# MCU152A_Connectors.net
KiCad netlist of a schematic drawn in Altium Designer
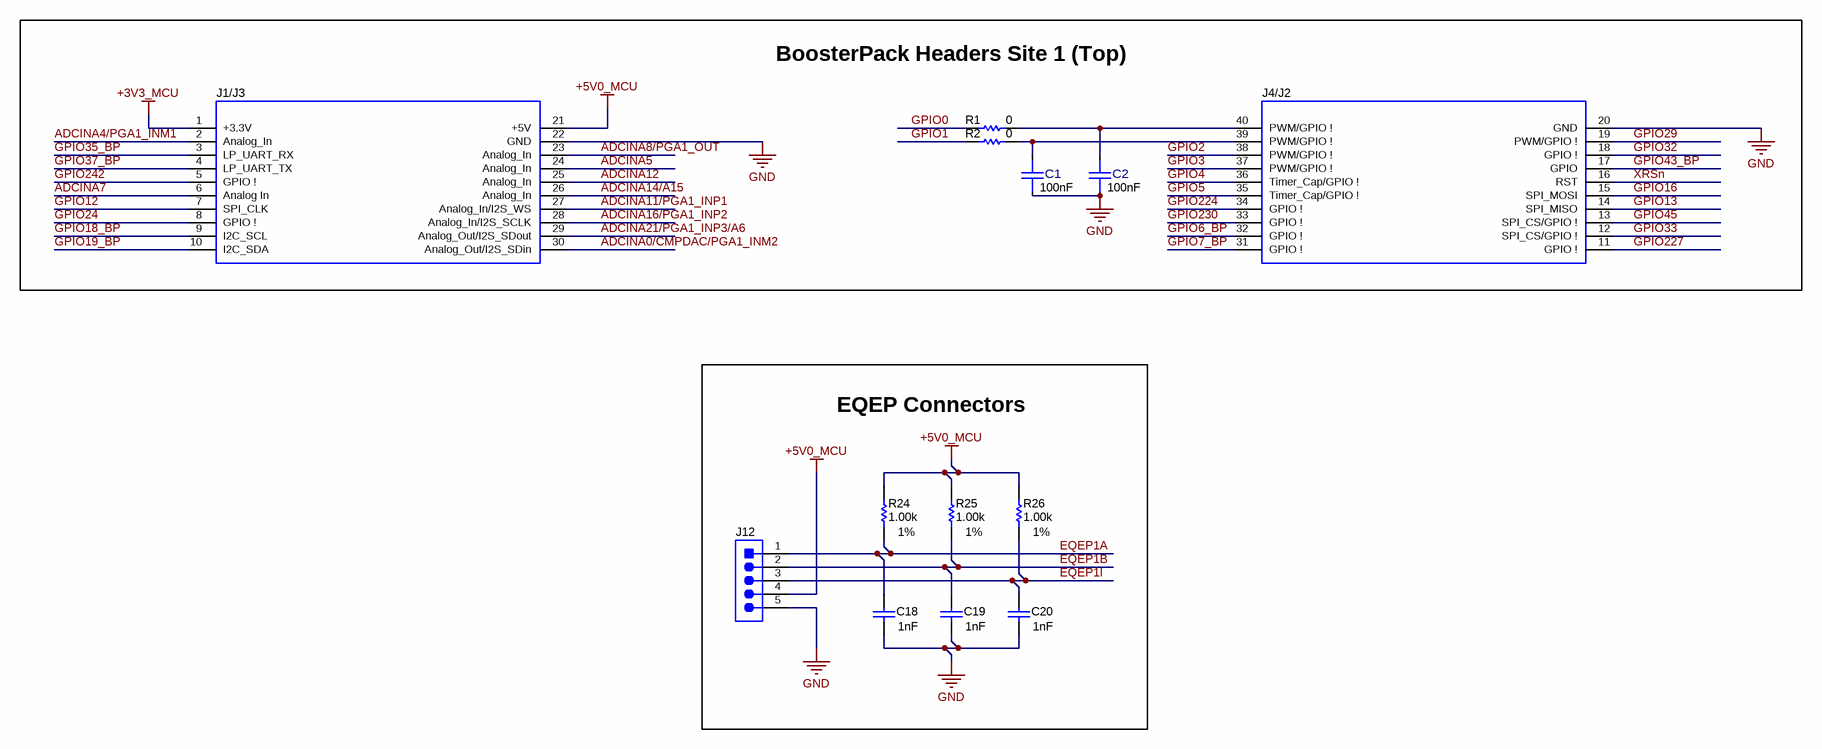
[diagram p0: MCU152A_Connectors.SchDoc]

(export (version "E")
  (design (tool "Eeschema 10.0.6"))
  (components
    (comp (ref "C1")
      (value "885012205018")
      (footprint "FP-885012205018_0402-MFG")
      (description "0.1µF ±10% 10V Ceramic Capacitor X7R 0402 (1005 Metric)")
      (fields
        (field (name "MANUFACTURER") "Wurth Electronics")
        (field (name "MOUSER PART NUMBER") "710-885012205018")
        (field (name "CAP_F") "100nF")
      )
      (libsource (lib "Altium Vault - TI") (part "SYM-885012205018"))
    )
    (comp (ref "C2")
      (value "885012205018")
      (footprint "FP-885012205018_0402-MFG")
      (description "0.1µF ±10% 10V Ceramic Capacitor X7R 0402 (1005 Metric)")
      (fields
        (field (name "MANUFACTURER") "Wurth Electronics")
        (field (name "MOUSER PART NUMBER") "710-885012205018")
        (field (name "CAP_F") "100nF")
      )
      (libsource (lib "Altium Vault - TI") (part "SYM-885012205018"))
    )
    (comp (ref "C18")
      (value "885012205061")
      (footprint "0402")
      (description "CAP, CERM, 1000 pF, 50 V, +/- 10%, X7R, 0402")
      (fields
        (field (name "MANUFACTURER") "Wurth Elektronik")
        (field (name "CAP_F") "1nF")
        (field (name "PUBLISHER") "Texas Instruments")
      )
      (libsource (lib "Altium Vault - TI") (part "Capacitor"))
    )
    (comp (ref "C19")
      (value "885012205061")
      (footprint "0402")
      (description "CAP, CERM, 1000 pF, 50 V, +/- 10%, X7R, 0402")
      (fields
        (field (name "MANUFACTURER") "Wurth Elektronik")
        (field (name "CAP_F") "1nF")
        (field (name "PUBLISHER") "Texas Instruments")
      )
      (libsource (lib "Altium Vault - TI") (part "Capacitor"))
    )
    (comp (ref "C20")
      (value "885012205061")
      (footprint "0402")
      (description "CAP, CERM, 1000 pF, 50 V, +/- 10%, X7R, 0402")
      (fields
        (field (name "MANUFACTURER") "Wurth Elektronik")
        (field (name "CAP_F") "1nF")
        (field (name "PUBLISHER") "Texas Instruments")
      )
      (libsource (lib "Altium Vault - TI") (part "Capacitor"))
    )
    (comp (ref "J1/J3")
      (value "SSQ-110-03-T-D")
      (footprint "BoosterPack_40pin_J1J3")
      (description "Receptacle, 2.54mm, 10x2, Tin, TH")
      (fields (field (name "ALTERNATE PARTNUMBER") "CRD-081413-A-G") (field (name "MANUFACTURER") "Samtec"))
      (libsource (lib "Altium Vault - TI") (part "BoosterPack_40pin_J1J3"))
    )
    (comp (ref "J4/J2")
      (value "SSQ-110-03-T-D")
      (footprint "BoosterPack_40pin_J2J4")
      (description "Receptacle, 2.54mm, 10x2, Tin, TH")
      (fields (field (name "ALTERNATE PARTNUMBER") "CRD-081413-A-G") (field (name "MANUFACTURER") "Samtec"))
      (libsource (lib "Altium Vault - TI") (part "BoosterPack_40pin_J2J4"))
    )
    (comp (ref "J12")
      (value "61300511121")
      (footprint "Wurth_61300511121")
      (description "Header, 2.54mm, 5x1, Gold, TH")
      (fields (field (name "MANUFACTURER") "Wurth Elektronik"))
      (libsource (lib "Altium Vault - TI") (part "Header_5x1"))
    )
    (comp (ref "R1")
      (value "RC0402JR-070RL")
      (footprint "0402")
      (description "RES, 0, 5%, 0.063 W, 0402")
      (fields
        (field (name "MANUFACTURER") "Yageo America")
        (field (name "VALUEDISPLAYED") "0")
        (field (name "PUBLISHER") "Texas Instruments")
      )
      (libsource (lib "Altium Vault - TI") (part "Resistor"))
    )
    (comp (ref "R2")
      (value "RC0402JR-070RL")
      (footprint "0402")
      (description "RES, 0, 5%, 0.063 W, 0402")
      (fields
        (field (name "MANUFACTURER") "Yageo America")
        (field (name "VALUEDISPLAYED") "0")
        (field (name "PUBLISHER") "Texas Instruments")
      )
      (libsource (lib "Altium Vault - TI") (part "Resistor"))
    )
    (comp (ref "R24")
      (value "CRCW04021K00FKED")
      (footprint "0402")
      (description "RES, 1.00 k, 1%, 0.063 W, AEC-Q200 Grade 0, 0402")
      (fields
        (field (name "VALUEDISPLAYED") "1.00k")
        (field (name "MANUFACTURER") "Vishay-Dale")
        (field (name "VALUE1") "1%")
      )
      (libsource (lib "Altium Vault - TI") (part "Resistor"))
    )
    (comp (ref "R25")
      (value "CRCW04021K00FKED")
      (footprint "0402")
      (description "RES, 1.00 k, 1%, 0.063 W, AEC-Q200 Grade 0, 0402")
      (fields
        (field (name "VALUEDISPLAYED") "1.00k")
        (field (name "MANUFACTURER") "Vishay-Dale")
        (field (name "VALUE1") "1%")
      )
      (libsource (lib "Altium Vault - TI") (part "Resistor"))
    )
    (comp (ref "R26")
      (value "CRCW04021K00FKED")
      (footprint "0402")
      (description "RES, 1.00 k, 1%, 0.063 W, AEC-Q200 Grade 0, 0402")
      (fields
        (field (name "VALUEDISPLAYED") "1.00k")
        (field (name "MANUFACTURER") "Vishay-Dale")
        (field (name "VALUE1") "1%")
      )
      (libsource (lib "Altium Vault - TI") (part "Resistor"))
    )
  )
  (nets
    (net (code "1") (name "+3V3_MCU") (class "Default")
      (node (ref "J1/J3") (pin "1") (pinfunction "+3.3V_1") (pintype "power_in"))
    )
    (net (code "2") (name "+5V0_MCU") (class "Default")
      (node (ref "J1/J3") (pin "21") (pinfunction "+5V_21") (pintype "power_in"))
      (node (ref "J12") (pin "4") (pinfunction "4_4") (pintype "passive"))
      (node (ref "R24") (pin "2") (pinfunction "2_2") (pintype "passive"))
      (node (ref "R25") (pin "2") (pinfunction "2_2") (pintype "passive"))
      (node (ref "R26") (pin "2") (pinfunction "2_2") (pintype "passive"))
    )
    (net (code "3") (name "/ADCINA0{slash}CMPDAC{slash}PGA1_INM2") (class "Default")
      (node (ref "J1/J3") (pin "30") (pinfunction "Analog_Out/I2S_SDin_30") (pintype "passive"))
    )
    (net (code "4") (name "/ADCINA4{slash}PGA1_INM1") (class "Default")
      (node (ref "J1/J3") (pin "2") (pinfunction "Analog_In_2") (pintype "passive"))
    )
    (net (code "5") (name "/ADCINA5") (class "Default")
      (node (ref "J1/J3") (pin "24") (pinfunction "Analog_In_24") (pintype "passive"))
    )
    (net (code "6") (name "/ADCINA7") (class "Default")
      (node (ref "J1/J3") (pin "6") (pinfunction "Analog_In_6") (pintype "passive"))
    )
    (net (code "7") (name "/ADCINA8{slash}PGA1_OUT") (class "Default")
      (node (ref "J1/J3") (pin "23") (pinfunction "Analog_In_23") (pintype "passive"))
    )
    (net (code "8") (name "/ADCINA11{slash}PGA1_INP1") (class "Default")
      (node (ref "J1/J3") (pin "27") (pinfunction "Analog_In/I2S_WS_27") (pintype "passive"))
    )
    (net (code "9") (name "/ADCINA12") (class "Default")
      (node (ref "J1/J3") (pin "25") (pinfunction "Analog_In_25") (pintype "passive"))
    )
    (net (code "10") (name "/ADCINA14{slash}A15") (class "Default")
      (node (ref "J1/J3") (pin "26") (pinfunction "Analog_In_26") (pintype "passive"))
    )
    (net (code "11") (name "/ADCINA16{slash}PGA1_INP2") (class "Default")
      (node (ref "J1/J3") (pin "28") (pinfunction "Analog_In/I2S_SCLK_28") (pintype "passive"))
    )
    (net (code "12") (name "/ADCINA21{slash}PGA1_INP3{slash}A6") (class "Default")
      (node (ref "J1/J3") (pin "29") (pinfunction "Analog_Out/I2S_SDout_29") (pintype "passive"))
    )
    (net (code "13") (name "/EQEP1A") (class "Default")
      (node (ref "C18") (pin "1") (pinfunction "1_1") (pintype "passive"))
      (node (ref "J12") (pin "1") (pinfunction "1_1") (pintype "passive"))
      (node (ref "R24") (pin "1") (pinfunction "1_1") (pintype "passive"))
    )
    (net (code "14") (name "/EQEP1B") (class "Default")
      (node (ref "C19") (pin "1") (pinfunction "1_1") (pintype "passive"))
      (node (ref "J12") (pin "2") (pinfunction "2_2") (pintype "passive"))
      (node (ref "R25") (pin "1") (pinfunction "1_1") (pintype "passive"))
    )
    (net (code "15") (name "/EQEP1I") (class "Default")
      (node (ref "C20") (pin "1") (pinfunction "1_1") (pintype "passive"))
      (node (ref "J12") (pin "3") (pinfunction "3_3") (pintype "passive"))
      (node (ref "R26") (pin "1") (pinfunction "1_1") (pintype "passive"))
    )
    (net (code "16") (name "/GPIO0") (class "Default")
      (node (ref "R1") (pin "1") (pinfunction "1_1") (pintype "passive"))
    )
    (net (code "17") (name "/GPIO1") (class "Default")
      (node (ref "R2") (pin "1") (pinfunction "1_1") (pintype "passive"))
    )
    (net (code "18") (name "/GPIO2") (class "Default")
      (node (ref "J4/J2") (pin "38") (pinfunction "PWM/GPIO_!_38") (pintype "passive"))
    )
    (net (code "19") (name "/GPIO3") (class "Default")
      (node (ref "J4/J2") (pin "37") (pinfunction "PWM/GPIO_!_37") (pintype "passive"))
    )
    (net (code "20") (name "/GPIO4") (class "Default")
      (node (ref "J4/J2") (pin "36") (pinfunction "Timer_Cap/GPIO_!_36") (pintype "passive"))
    )
    (net (code "21") (name "/GPIO5") (class "Default")
      (node (ref "J4/J2") (pin "35") (pinfunction "Timer_Cap/GPIO_!_35") (pintype "passive"))
    )
    (net (code "22") (name "/GPIO6_BP") (class "Default")
      (node (ref "J4/J2") (pin "32") (pinfunction "GPIO_!_32") (pintype "passive"))
    )
    (net (code "23") (name "/GPIO7_BP") (class "Default")
      (node (ref "J4/J2") (pin "31") (pinfunction "GPIO_!_31") (pintype "passive"))
    )
    (net (code "24") (name "/GPIO12") (class "Default")
      (node (ref "J1/J3") (pin "7") (pinfunction "SPI_CLK_7") (pintype "passive"))
    )
    (net (code "25") (name "/GPIO13") (class "Default")
      (node (ref "J4/J2") (pin "14") (pinfunction "SPI_MISO_14") (pintype "passive"))
    )
    (net (code "26") (name "/GPIO16") (class "Default")
      (node (ref "J4/J2") (pin "15") (pinfunction "SPI_MOSI_15") (pintype "passive"))
    )
    (net (code "27") (name "/GPIO18_BP") (class "Default")
      (node (ref "J1/J3") (pin "9") (pinfunction "I2C_SCL_9") (pintype "passive"))
    )
    (net (code "28") (name "/GPIO19_BP") (class "Default")
      (node (ref "J1/J3") (pin "10") (pinfunction "I2C_SDA_10") (pintype "passive"))
    )
    (net (code "29") (name "/GPIO24") (class "Default")
      (node (ref "J1/J3") (pin "8") (pinfunction "GPIO_!_8") (pintype "passive"))
    )
    (net (code "30") (name "/GPIO29") (class "Default")
      (node (ref "J4/J2") (pin "19") (pinfunction "PWM/GPIO_!_19") (pintype "passive"))
    )
    (net (code "31") (name "/GPIO32") (class "Default")
      (node (ref "J4/J2") (pin "18") (pinfunction "GPIO_!_18") (pintype "passive"))
    )
    (net (code "32") (name "/GPIO33") (class "Default")
      (node (ref "J4/J2") (pin "12") (pinfunction "SPI_CS/GPIO_!_12") (pintype "passive"))
    )
    (net (code "33") (name "/GPIO35_BP") (class "Default")
      (node (ref "J1/J3") (pin "3") (pinfunction "LP_UART_RX_3") (pintype "passive"))
    )
    (net (code "34") (name "/GPIO37_BP") (class "Default")
      (node (ref "J1/J3") (pin "4") (pinfunction "LP_UART_TX_4") (pintype "passive"))
    )
    (net (code "35") (name "/GPIO43_BP") (class "Default")
      (node (ref "J4/J2") (pin "17") (pinfunction "GPIO_17") (pintype "passive"))
    )
    (net (code "36") (name "/GPIO45") (class "Default")
      (node (ref "J4/J2") (pin "13") (pinfunction "SPI_CS/GPIO_!_13") (pintype "passive"))
    )
    (net (code "37") (name "/GPIO224") (class "Default")
      (node (ref "J4/J2") (pin "34") (pinfunction "GPIO_!_34") (pintype "passive"))
    )
    (net (code "38") (name "/GPIO227") (class "Default")
      (node (ref "J4/J2") (pin "11") (pinfunction "GPIO_!_11") (pintype "passive"))
    )
    (net (code "39") (name "/GPIO230") (class "Default")
      (node (ref "J4/J2") (pin "33") (pinfunction "GPIO_!_33") (pintype "passive"))
    )
    (net (code "40") (name "/GPIO242") (class "Default")
      (node (ref "J1/J3") (pin "5") (pinfunction "GPIO_!_5") (pintype "passive"))
    )
    (net (code "41") (name "/XRSn") (class "Default")
      (node (ref "J4/J2") (pin "16") (pinfunction "RST_16") (pintype "passive"))
    )
    (net (code "42") (name "GND") (class "Default")
      (node (ref "C1") (pin "1") (pinfunction "1_1") (pintype "passive"))
      (node (ref "C18") (pin "2") (pinfunction "2_2") (pintype "passive"))
      (node (ref "C19") (pin "2") (pinfunction "2_2") (pintype "passive"))
      (node (ref "C2") (pin "1") (pinfunction "1_1") (pintype "passive"))
      (node (ref "C20") (pin "2") (pinfunction "2_2") (pintype "passive"))
      (node (ref "J1/J3") (pin "22") (pinfunction "GND_22") (pintype "power_in"))
      (node (ref "J12") (pin "5") (pinfunction "5_5") (pintype "passive"))
      (node (ref "J4/J2") (pin "20") (pinfunction "GND_20") (pintype "power_in"))
    )
    (net (code "43") (name "Net-(C1-Pad2)") (class "Default")
      (node (ref "C1") (pin "2") (pinfunction "2_2") (pintype "passive"))
      (node (ref "J4/J2") (pin "39") (pinfunction "PWM/GPIO_!_39") (pintype "passive"))
      (node (ref "R2") (pin "2") (pinfunction "2_2") (pintype "passive"))
    )
    (net (code "44") (name "Net-(C2-Pad2)") (class "Default")
      (node (ref "C2") (pin "2") (pinfunction "2_2") (pintype "passive"))
      (node (ref "J4/J2") (pin "40") (pinfunction "PWM/GPIO_!_40") (pintype "passive"))
      (node (ref "R1") (pin "2") (pinfunction "2_2") (pintype "passive"))
    )
  )
)
